# Amplifier-LM386.net
KiCad netlist of a schematic drawn in Altium Designer
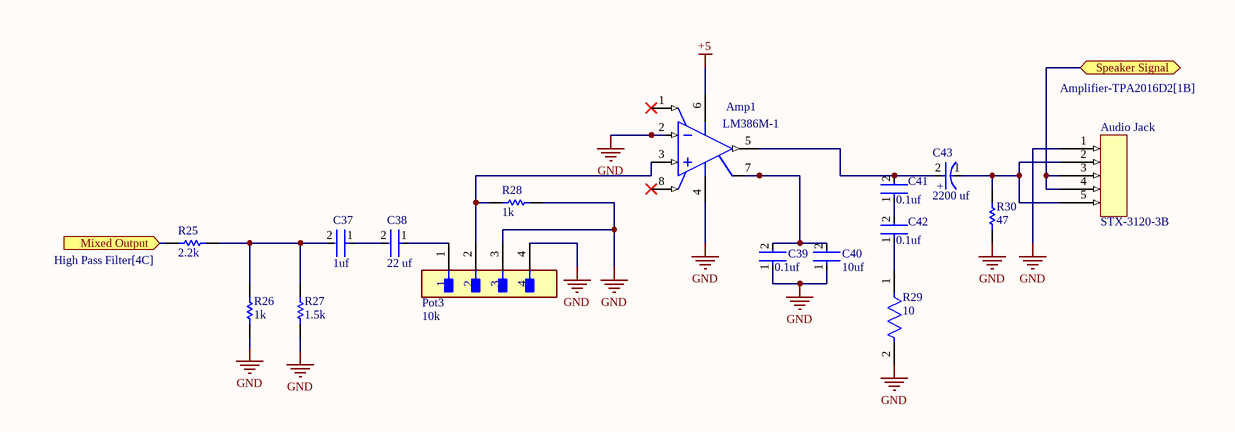
[diagram p0: Amplifier-LM386.SchDoc]

(export (version "E")
  (design (tool "Eeschema 10.0.6"))
  (components
    (comp (ref "Amp1")
      (value "LM386M-1")
      (footprint "TI-D8_M")
      (description "Low Voltage Audio Power Amplifier, 0 to 70 degC, 8-pin SOIC (D8), Green (RoHS & no Sb/Br)")
      (fields (field (name "PARTNUMBER") "LM386M-1/NOPB") (field (name "MANUFACTURER") "Texas Instruments"))
      (libsource (lib "Altium Content Vault") (part "TI-LM386undefined"))
    )
    (comp (ref "Audio Jack")
      (value "STX-3120-3B")
      (footprint "STX3100")
      (description "3 Pole(s), Female, Solder Terminal, Locking, Jack")
      (libsource (lib "Ryamgordon") (part "STX-3120-3B"))
    )
    (comp (ref "C37")
      (value "1uf")
      (footprint "FP-K105Z20Y5VF5TL2-MFG")
      (description "CAP CER 1UF 50V Y5V RADIAL")
      (fields
        (field (name "TOLERANCE") "-20+80%")
        (field (name "OCTOPART") "https://octopart.com/k105z20y5vf5tl2-vishay-39475252")
      )
      (libsource (lib "Altium Content Vault") (part "11868f565c42a9108669ba33697ecf6"))
    )
    (comp (ref "C38")
      (value "22 uf")
      (footprint "FP-RCEWM1-MFG")
      (description "CAP CER 22UF 25V X7R RADIAL")
      (fields (field (name "TOLERANCE") "20%"))
      (libsource (lib "Altium Content Vault") (part "02cd4be3c70576c341d710602a673aa"))
    )
    (comp (ref "C39")
      (value "0.1uf")
      (footprint "FP-SR20-MFG")
      (description "CAP CER 0.1UF 50V X7R RADIAL")
      (fields (field (name "VOLTAGE") "50V") (field (name "TOLERANCE") "10%"))
      (libsource (lib "Altium Content Vault") (part "11868f565c42a9108669ba33697ecf6"))
    )
    (comp (ref "C40")
      (value "10uf")
      (footprint "FP-RCE3DB-MFG")
      (description "Cap Ceramic 10uF 25V X7R ±10% Radial 2.5mm +125°C Automotive Ammo Pack")
      (fields (field (name "TOLERANCE") "10%"))
      (libsource (lib "Altium Content Vault") (part "b4654b650e69147ec39a6b967a45e02"))
    )
    (comp (ref "C41")
      (value "0.1uf")
      (footprint "FP-SR20-MFG")
      (description "CAP CER 0.1UF 50V X7R RADIAL")
      (fields (field (name "VOLTAGE") "50V") (field (name "TOLERANCE") "10%"))
      (libsource (lib "Altium Content Vault") (part "11868f565c42a9108669ba33697ecf6"))
    )
    (comp (ref "C42")
      (value "0.1uf")
      (footprint "FP-SR20-MFG")
      (description "CAP CER 0.1UF 50V X7R RADIAL")
      (fields (field (name "VOLTAGE") "50V") (field (name "TOLERANCE") "10%"))
      (libsource (lib "Altium Content Vault") (part "11868f565c42a9108669ba33697ecf6"))
    )
    (comp (ref "C43")
      (value "2200 uf")
      (footprint "FP-RAD-TH-D_10_0_5-L_16_1-MFG")
      (description "Aluminum Electrolytic Capacitors (Radial Lead Type) 220uF ±20% 50V")
      (fields (field (name "TOLERANCE") "20%"))
      (libsource (lib "Altium Content Vault") (part "a00bbbee19879c290e62620ae7e47b1"))
    )
    (comp (ref "Pot3")
      (value "10k")
      (footprint "FP-B4B-XH-A_LF_SN-MFG")
      (description "CONN HEADER VERT 4POS 2.5MM")
      (libsource (lib "Altium Content Vault") (part "299a8cea1bdcbc3624fe62c390fa72c"))
    )
    (comp (ref "R25")
      (value "2.2k")
      (footprint "RESC2013X60X40LL20T25")
      (fields (field (name "MANUFACTURER") "Panasonic") (field (name "PART NUMBER") "ERA6AEB222V"))
      (libsource (lib "Altium Content Vault") (part "RES"))
    )
    (comp (ref "R26")
      (value "1k")
      (footprint "RESC2013X70X40ML20T20")
      (description "Chip Resistor, 1 KOhm, +/- 1%, 0.125 W, -55 to 155 degC, 0805 (2012 Metric), RoHS, Tape and Reel")
      (fields (field (name "MANUFACTURER") "Panasonic"))
      (libsource (lib "Altium Content Vault") (part "RES-2"))
    )
    (comp (ref "R27")
      (value "1.5k")
      (footprint "RESC2013X60X40LL20T25")
      (fields (field (name "MANUFACTURER") "Panasonic") (field (name "PART NUMBER") "ERA6AEB152V"))
      (libsource (lib "Altium Content Vault") (part "RES"))
    )
    (comp (ref "R28")
      (value "1k")
      (footprint "RESC2013X70X40ML20T20")
      (description "Chip Resistor, 1 KOhm, +/- 1%, 0.125 W, -55 to 155 degC, 0805 (2012 Metric), RoHS, Tape and Reel")
      (fields (field (name "MANUFACTURER") "Panasonic"))
      (libsource (lib "Altium Content Vault") (part "RES-2"))
    )
    (comp (ref "R29")
      (value "10")
      (footprint "FP-RN732A-MFG")
      (description "SMD Chip Resistor, Thin Film, 10Ω, 100 V, 0805 [2012 Metric], 100 mW, 0.1%, RN73 Series")
      (fields
        (field (name "MANUFACTURER") "TE Connectivity")
        (field (name "MANUFACTURER PART NUMBER") "RN73C2A10RBTG")
      )
      (libsource (lib "Altium Content Vault") (part "1029c3af85768c4190bb7ad29bc67b5"))
    )
    (comp (ref "R30")
      (value "47")
      (footprint "RESC2013X60X40ML20T25")
      (fields (field (name "MANUFACTURER") "Panasonic") (field (name "PART NUMBER") "ERA6AEB470V"))
      (libsource (lib "Altium Content Vault") (part "RES"))
    )
  )
  (nets
    (net (code "1") (name "+5") (class "Default")
      (node (ref "Amp1") (pin "6") (pinfunction "VS_6") (pintype "power_in"))
    )
    (net (code "2") (name "/Mixed Output") (class "Default")
      (node (ref "R25") (pin "2") (pinfunction "2_2") (pintype "passive"))
    )
    (net (code "3") (name "/Speaker Signal") (class "Default")
      (node (ref "Audio Jack") (pin "3") (pintype "input"))
      (node (ref "Audio Jack") (pin "4") (pintype "input"))
    )
    (net (code "4") (name "GND") (class "Default")
      (node (ref "Amp1") (pin "2") (pinfunction "IN-_2") (pintype "input"))
      (node (ref "Amp1") (pin "4") (pinfunction "GND_4") (pintype "power_in"))
      (node (ref "Audio Jack") (pin "1") (pintype "input"))
      (node (ref "C39") (pin "1") (pinfunction "1_1") (pintype "passive"))
      (node (ref "C40") (pin "1") (pinfunction "1_1") (pintype "passive"))
      (node (ref "Pot3") (pin "3") (pinfunction "3_3") (pintype "passive"))
      (node (ref "Pot3") (pin "4") (pinfunction "4_4") (pintype "passive"))
      (node (ref "R26") (pin "1") (pinfunction "1_1") (pintype "passive"))
      (node (ref "R27") (pin "1") (pinfunction "1_1") (pintype "passive"))
      (node (ref "R28") (pin "2") (pinfunction "2_2") (pintype "passive"))
      (node (ref "R29") (pin "2") (pinfunction "2_2") (pintype "passive"))
      (node (ref "R30") (pin "1") (pinfunction "1_1") (pintype "passive"))
    )
    (net (code "5") (name "Net-(Amp1-BYPASS)") (class "Default")
      (node (ref "Amp1") (pin "7") (pinfunction "BYPASS_7") (pintype "passive"))
      (node (ref "C39") (pin "2") (pinfunction "2_2") (pintype "passive"))
      (node (ref "C40") (pin "2") (pinfunction "2_2") (pintype "passive"))
    )
    (net (code "6") (name "Net-(Amp1-IN+)") (class "Default")
      (node (ref "Amp1") (pin "3") (pinfunction "IN+_3") (pintype "input"))
      (node (ref "Pot3") (pin "2") (pinfunction "2_2") (pintype "passive"))
      (node (ref "R28") (pin "1") (pinfunction "1_1") (pintype "passive"))
    )
    (net (code "7") (name "Net-(Amp1-VOUT)") (class "Default")
      (node (ref "Amp1") (pin "5") (pinfunction "VOUT_5") (pintype "output"))
      (node (ref "C41") (pin "2") (pinfunction "2_2") (pintype "passive"))
      (node (ref "C43") (pin "2") (pinfunction "A_2") (pintype "passive"))
    )
    (net (code "8") (name "Net-(C37-Pad1)") (class "Default")
      (node (ref "C37") (pin "1") (pinfunction "1_1") (pintype "passive"))
      (node (ref "C38") (pin "2") (pinfunction "2_2") (pintype "passive"))
    )
    (net (code "9") (name "Net-(C37-Pad2)") (class "Default")
      (node (ref "C37") (pin "2") (pinfunction "2_2") (pintype "passive"))
      (node (ref "R25") (pin "1") (pinfunction "1_1") (pintype "passive"))
      (node (ref "R26") (pin "2") (pinfunction "2_2") (pintype "passive"))
      (node (ref "R27") (pin "2") (pinfunction "2_2") (pintype "passive"))
    )
    (net (code "10") (name "Net-(C38-Pad1)") (class "Default")
      (node (ref "C38") (pin "1") (pinfunction "1_1") (pintype "passive"))
      (node (ref "Pot3") (pin "1") (pinfunction "1_1") (pintype "passive"))
    )
    (net (code "11") (name "Net-(C41-Pad1)") (class "Default")
      (node (ref "C41") (pin "1") (pinfunction "1_1") (pintype "passive"))
      (node (ref "C42") (pin "2") (pinfunction "2_2") (pintype "passive"))
    )
    (net (code "12") (name "Net-(C42-Pad1)") (class "Default")
      (node (ref "C42") (pin "1") (pinfunction "1_1") (pintype "passive"))
      (node (ref "R29") (pin "1") (pinfunction "1_1") (pintype "passive"))
    )
    (net (code "13") (name "Net-(C43-C)") (class "Default")
      (node (ref "Audio Jack") (pin "2") (pintype "input"))
      (node (ref "Audio Jack") (pin "5") (pintype "input"))
      (node (ref "C43") (pin "1") (pinfunction "C_1") (pintype "passive"))
      (node (ref "R30") (pin "2") (pinfunction "2_2") (pintype "passive"))
    )
    (net (code "14") (name "unconnected-(Amp1-GAIN-Pad1)") (class "Default")
      (node (ref "Amp1") (pin "1") (pinfunction "GAIN_1") (pintype "input+no_connect"))
    )
    (net (code "15") (name "unconnected-(Amp1-GAIN-Pad8)") (class "Default")
      (node (ref "Amp1") (pin "8") (pinfunction "GAIN_8") (pintype "input+no_connect"))
    )
  )
)
